# main.net
KiCad netlist of a schematic drawn in EAGLE
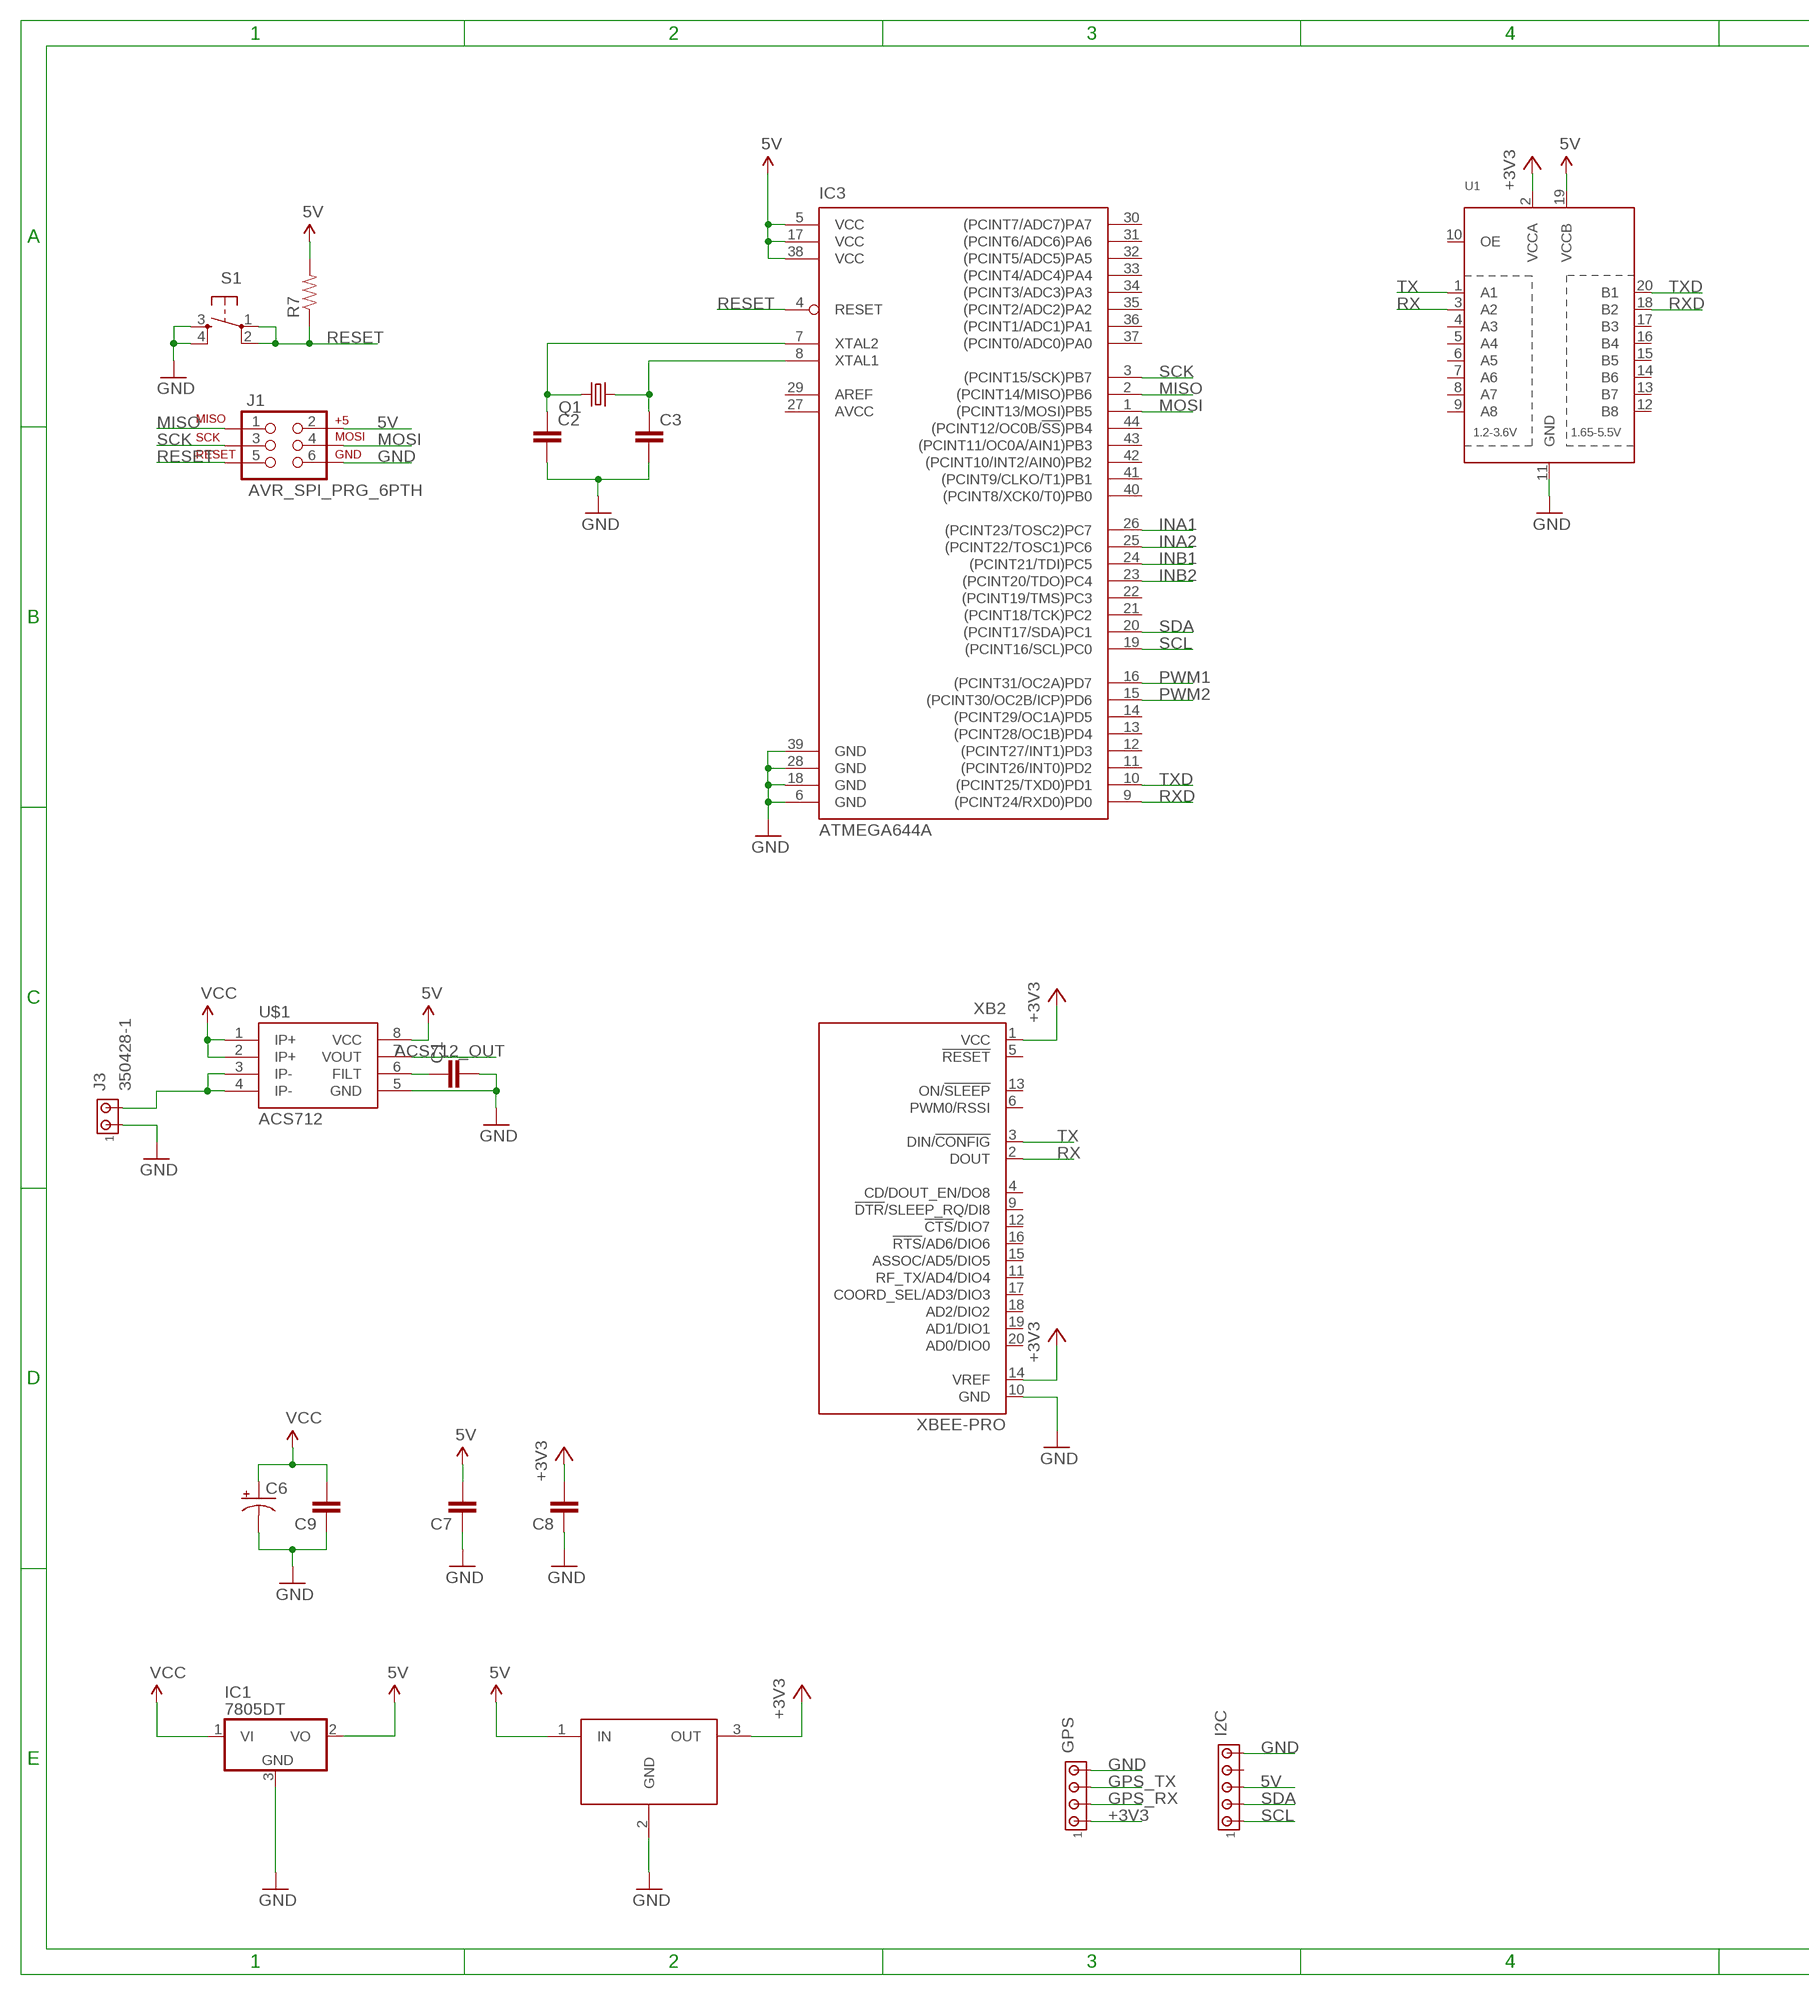
[diagram p0: schematic, sheet 1, part 1 of 2]
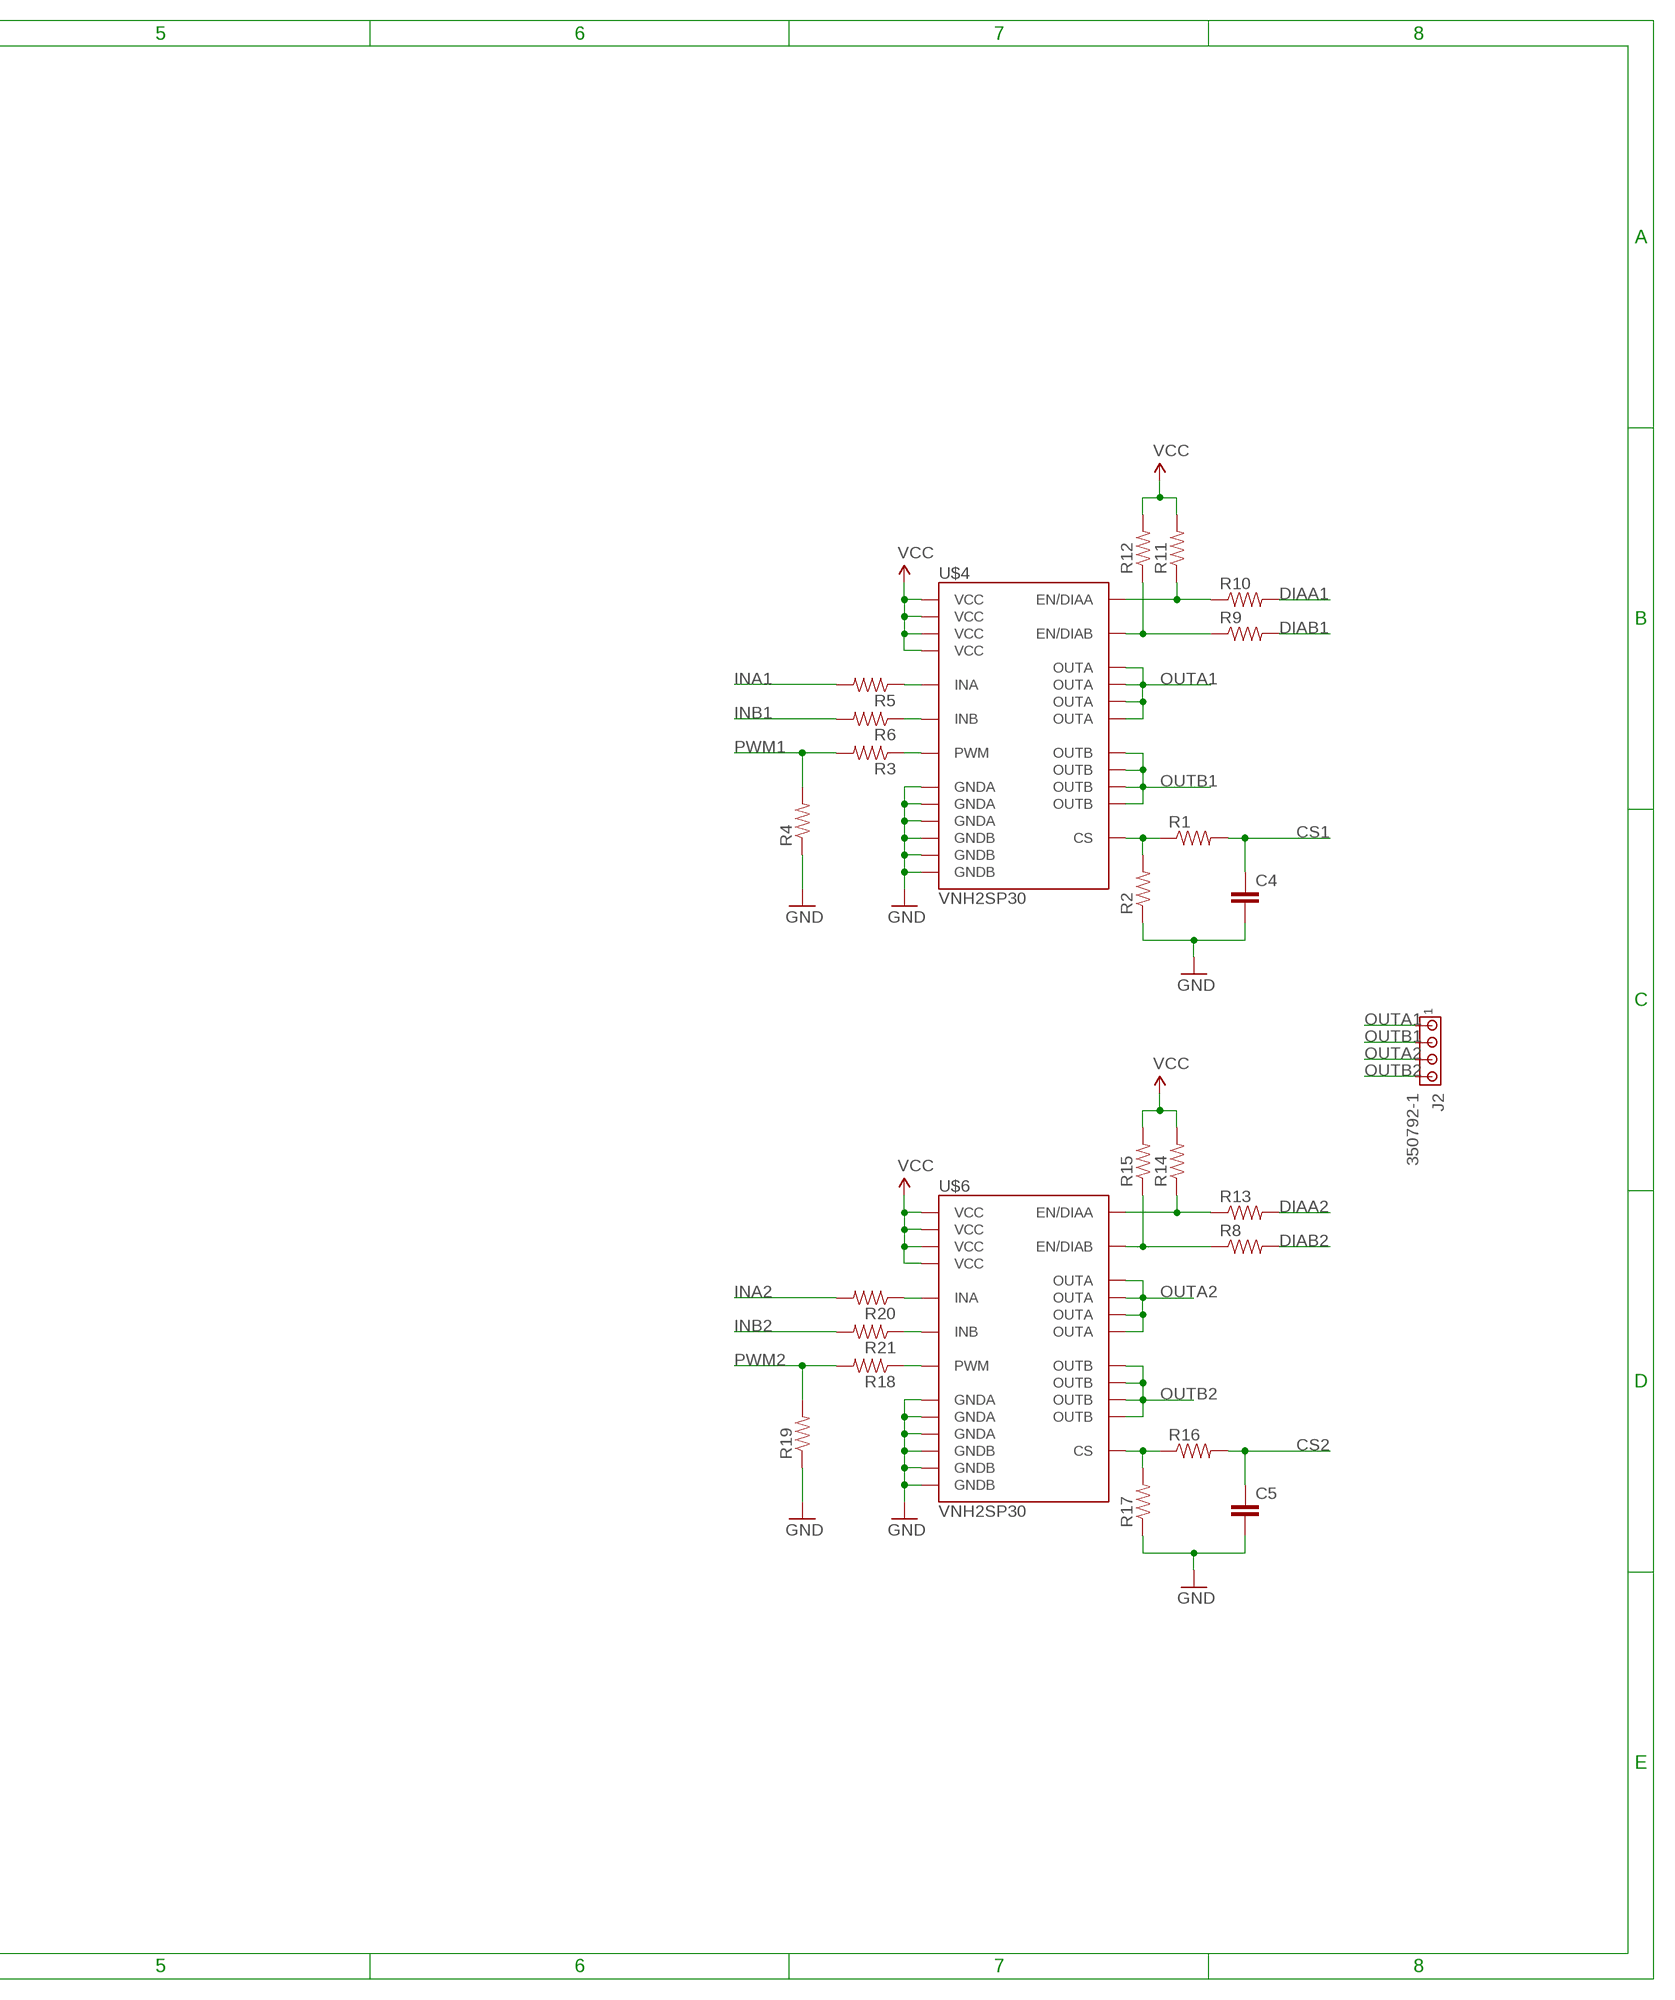
[diagram p1: schematic, sheet 1, part 2 of 2]

(export (version "E")
  (design (tool "Eeschema 10.0.6"))
  (components
    (comp (ref "C1")
      (value "CAP0603-CAP")
      (footprint "eagle-import:0603-CAP")
      (libsource (lib "eagle-import") (part "CAP0603-CAP"))
    )
    (comp (ref "C2")
      (value "CAP0603-CAP")
      (footprint "eagle-import:0603-CAP")
      (libsource (lib "eagle-import") (part "CAP0603-CAP"))
    )
    (comp (ref "C3")
      (value "CAP0603-CAP")
      (footprint "eagle-import:0603-CAP")
      (libsource (lib "eagle-import") (part "CAP0603-CAP"))
    )
    (comp (ref "C4")
      (value "CAP0603-CAP")
      (footprint "eagle-import:0603-CAP")
      (libsource (lib "eagle-import") (part "CAP0603-CAP"))
    )
    (comp (ref "C5")
      (value "CAP0603-CAP")
      (footprint "eagle-import:0603-CAP")
      (libsource (lib "eagle-import") (part "CAP0603-CAP"))
    )
    (comp (ref "C6")
      (value "CPOL-US140CLH-1010")
      (footprint "eagle-import:140CLH-1010")
      (libsource (lib "eagle-import") (part "CPOL-US140CLH-1010"))
    )
    (comp (ref "C7")
      (value "CAP0603-CAP")
      (footprint "eagle-import:0603-CAP")
      (libsource (lib "eagle-import") (part "CAP0603-CAP"))
    )
    (comp (ref "C8")
      (value "CAP0603-CAP")
      (footprint "eagle-import:0603-CAP")
      (libsource (lib "eagle-import") (part "CAP0603-CAP"))
    )
    (comp (ref "C9")
      (value "CAP0603-CAP")
      (footprint "eagle-import:0603-CAP")
      (libsource (lib "eagle-import") (part "CAP0603-CAP"))
    )
    (comp (ref "GPS")
      (value "MTA04-100")
      (footprint "eagle-import:10X04MTA")
      (libsource (lib "eagle-import") (part "MTA04-100"))
    )
    (comp (ref "I2C")
      (value "MTA05-100")
      (footprint "eagle-import:10X05MTA")
      (libsource (lib "eagle-import") (part "MTA05-100"))
    )
    (comp (ref "IC1")
      (value "7805DT")
      (footprint "eagle-import:TO252")
      (libsource (lib "eagle-import") (part "78DT05"))
    )
    (comp (ref "IC3")
      (value "ATMEGA644A")
      (footprint "eagle-import:TQFP44")
      (fields (field (name "MPN") "ATMEGA644PV-10AU"))
      (libsource (lib "eagle-import") (part "ATMEGA644A"))
    )
    (comp (ref "J1")
      (value "AVR_SPI_PRG_6PTH")
      (footprint "eagle-import:2X3")
      (libsource (lib "eagle-import") (part "AVR_SPI_PRG_6PTH"))
    )
    (comp (ref "J2")
      (value "350792-1")
      (footprint "eagle-import:350792-1")
      (libsource (lib "eagle-import") (part "350792-1"))
    )
    (comp (ref "J3")
      (value "350428-1")
      (footprint "eagle-import:350428-1")
      (libsource (lib "eagle-import") (part "350428-1"))
    )
    (comp (ref "LM3940(SOT223)")
      (value "LM3940 SOT223")
      (footprint "eagle-import:SOT223")
      (libsource (lib "eagle-import") (part "LM3940IMP-3.3"))
    )
    (comp (ref "Q1")
      (value "CRYSTALHC49UP")
      (footprint "eagle-import:HC49UP")
      (libsource (lib "eagle-import") (part "CRYSTALHC49UP"))
    )
    (comp (ref "R1")
      (value "RESISTOR0603-RES")
      (footprint "eagle-import:0603-RES")
      (libsource (lib "eagle-import") (part "RESISTOR0603-RES"))
    )
    (comp (ref "R2")
      (value "RESISTOR0603-RES")
      (footprint "eagle-import:0603-RES")
      (libsource (lib "eagle-import") (part "RESISTOR0603-RES"))
    )
    (comp (ref "R3")
      (value "RESISTOR0603-RES")
      (footprint "eagle-import:0603-RES")
      (libsource (lib "eagle-import") (part "RESISTOR0603-RES"))
    )
    (comp (ref "R4")
      (value "RESISTOR0603-RES")
      (footprint "eagle-import:0603-RES")
      (libsource (lib "eagle-import") (part "RESISTOR0603-RES"))
    )
    (comp (ref "R5")
      (value "RESISTOR0603-RES")
      (footprint "eagle-import:0603-RES")
      (libsource (lib "eagle-import") (part "RESISTOR0603-RES"))
    )
    (comp (ref "R6")
      (value "RESISTOR0603-RES")
      (footprint "eagle-import:0603-RES")
      (libsource (lib "eagle-import") (part "RESISTOR0603-RES"))
    )
    (comp (ref "R7")
      (value "RESISTOR0603-RES")
      (footprint "eagle-import:0603-RES")
      (libsource (lib "eagle-import") (part "RESISTOR0603-RES"))
    )
    (comp (ref "R8")
      (value "RESISTOR0603-RES")
      (footprint "eagle-import:0603-RES")
      (libsource (lib "eagle-import") (part "RESISTOR0603-RES"))
    )
    (comp (ref "R9")
      (value "RESISTOR0603-RES")
      (footprint "eagle-import:0603-RES")
      (libsource (lib "eagle-import") (part "RESISTOR0603-RES"))
    )
    (comp (ref "R10")
      (value "RESISTOR0603-RES")
      (footprint "eagle-import:0603-RES")
      (libsource (lib "eagle-import") (part "RESISTOR0603-RES"))
    )
    (comp (ref "R11")
      (value "RESISTOR0603-RES")
      (footprint "eagle-import:0603-RES")
      (libsource (lib "eagle-import") (part "RESISTOR0603-RES"))
    )
    (comp (ref "R12")
      (value "RESISTOR0603-RES")
      (footprint "eagle-import:0603-RES")
      (libsource (lib "eagle-import") (part "RESISTOR0603-RES"))
    )
    (comp (ref "R13")
      (value "RESISTOR0603-RES")
      (footprint "eagle-import:0603-RES")
      (libsource (lib "eagle-import") (part "RESISTOR0603-RES"))
    )
    (comp (ref "R14")
      (value "RESISTOR0603-RES")
      (footprint "eagle-import:0603-RES")
      (libsource (lib "eagle-import") (part "RESISTOR0603-RES"))
    )
    (comp (ref "R15")
      (value "RESISTOR0603-RES")
      (footprint "eagle-import:0603-RES")
      (libsource (lib "eagle-import") (part "RESISTOR0603-RES"))
    )
    (comp (ref "R16")
      (value "RESISTOR0603-RES")
      (footprint "eagle-import:0603-RES")
      (libsource (lib "eagle-import") (part "RESISTOR0603-RES"))
    )
    (comp (ref "R17")
      (value "RESISTOR0603-RES")
      (footprint "eagle-import:0603-RES")
      (libsource (lib "eagle-import") (part "RESISTOR0603-RES"))
    )
    (comp (ref "R18")
      (value "RESISTOR0603-RES")
      (footprint "eagle-import:0603-RES")
      (libsource (lib "eagle-import") (part "RESISTOR0603-RES"))
    )
    (comp (ref "R19")
      (value "RESISTOR0603-RES")
      (footprint "eagle-import:0603-RES")
      (libsource (lib "eagle-import") (part "RESISTOR0603-RES"))
    )
    (comp (ref "R20")
      (value "RESISTOR0603-RES")
      (footprint "eagle-import:0603-RES")
      (libsource (lib "eagle-import") (part "RESISTOR0603-RES"))
    )
    (comp (ref "R21")
      (value "RESISTOR0603-RES")
      (footprint "eagle-import:0603-RES")
      (libsource (lib "eagle-import") (part "RESISTOR0603-RES"))
    )
    (comp (ref "S1")
      (value "TAC_SWITCHSMD")
      (footprint "eagle-import:TACTILE_SWITCH_SMD")
      (libsource (lib "eagle-import") (part "TAC_SWITCHSMD"))
    )
    (comp (ref "U$1")
      (value "ACS712")
      (footprint "eagle-import:SO08")
      (libsource (lib "eagle-import") (part "ACS712"))
    )
    (comp (ref "U$4")
      (value "VNH2SP30")
      (footprint "eagle-import:VNH2SP30")
      (libsource (lib "eagle-import") (part "VNH2SP30"))
    )
    (comp (ref "U$6")
      (value "VNH2SP30")
      (footprint "eagle-import:VNH2SP30")
      (libsource (lib "eagle-import") (part "VNH2SP30"))
    )
    (comp (ref "U1")
      (value "TXB0108PWR")
      (footprint "eagle-import:TSSOP20")
      (libsource (lib "eagle-import") (part "TXB0108PWR"))
    )
    (comp (ref "XB2")
      (value "XBEE-PRO")
      (footprint "eagle-import:XBEE-PRO")
      (fields (field (name "MPN") "XBP24-AWI-001"))
      (libsource (lib "eagle-import") (part "XBEE-PRO"))
    )
  )
  (nets
    (net (code "1") (name "+3V3") (class "Default")
      (node (ref "C8") (pin "2") (pinfunction "2_2") (pintype "passive"))
      (node (ref "GPS") (pin "1") (pinfunction "1_1") (pintype "passive"))
      (node (ref "LM3940(SOT223)") (pin "3") (pinfunction "OUT_3") (pintype "power_in"))
      (node (ref "U1") (pin "2") (pinfunction "VCCA_2") (pintype "bidirectional"))
      (node (ref "XB2") (pin "1") (pinfunction "VCC_1") (pintype "power_in"))
      (node (ref "XB2") (pin "14") (pinfunction "VREF_14") (pintype "input"))
    )
    (net (code "2") (name "/ACS712_OUT") (class "Default")
      (node (ref "U$1") (pin "7") (pinfunction "VOUT_7") (pintype "bidirectional"))
    )
    (net (code "3") (name "/AVCC") (class "Default")
      (node (ref "IC3") (pin "27") (pinfunction "AVCC_27") (pintype "power_in"))
    )
    (net (code "4") (name "/CS1") (class "Default")
      (node (ref "C4") (pin "1") (pinfunction "1_1") (pintype "passive"))
      (node (ref "R1") (pin "2") (pinfunction "2_2") (pintype "passive"))
    )
    (net (code "5") (name "/CS2") (class "Default")
      (node (ref "C5") (pin "1") (pinfunction "1_1") (pintype "passive"))
      (node (ref "R16") (pin "2") (pinfunction "2_2") (pintype "passive"))
    )
    (net (code "6") (name "/DIAA1") (class "Default")
      (node (ref "R10") (pin "2") (pinfunction "2_2") (pintype "passive"))
    )
    (net (code "7") (name "/DIAA2") (class "Default")
      (node (ref "R13") (pin "2") (pinfunction "2_2") (pintype "passive"))
    )
    (net (code "8") (name "/DIAB1") (class "Default")
      (node (ref "R9") (pin "2") (pinfunction "2_2") (pintype "passive"))
    )
    (net (code "9") (name "/DIAB2") (class "Default")
      (node (ref "R8") (pin "2") (pinfunction "2_2") (pintype "passive"))
    )
    (net (code "10") (name "/GPS_RX") (class "Default")
      (node (ref "GPS") (pin "2") (pinfunction "2_2") (pintype "passive"))
    )
    (net (code "11") (name "/GPS_TX") (class "Default")
      (node (ref "GPS") (pin "3") (pinfunction "3_3") (pintype "passive"))
    )
    (net (code "12") (name "/INA1") (class "Default")
      (node (ref "IC3") (pin "26") (pinfunction "(PCINT23/TOSC2)PC7_26") (pintype "output"))
      (node (ref "R5") (pin "2") (pinfunction "2_2") (pintype "passive"))
    )
    (net (code "13") (name "/INA2") (class "Default")
      (node (ref "IC3") (pin "25") (pinfunction "(PCINT22/TOSC1)PC6_25") (pintype "output"))
      (node (ref "R20") (pin "2") (pinfunction "2_2") (pintype "passive"))
    )
    (net (code "14") (name "/INB1") (class "Default")
      (node (ref "IC3") (pin "24") (pinfunction "(PCINT21/TDI)PC5_24") (pintype "output"))
      (node (ref "R6") (pin "2") (pinfunction "2_2") (pintype "passive"))
    )
    (net (code "15") (name "/INB2") (class "Default")
      (node (ref "IC3") (pin "23") (pinfunction "(PCINT20/TDO)PC4_23") (pintype "output"))
      (node (ref "R21") (pin "2") (pinfunction "2_2") (pintype "passive"))
    )
    (net (code "16") (name "/MISO") (class "Default")
      (node (ref "IC3") (pin "2") (pinfunction "(PCINT14/MISO)PB6_2") (pintype "bidirectional"))
      (node (ref "J1") (pin "1") (pinfunction "1_1") (pintype "passive"))
    )
    (net (code "17") (name "/MOSI") (class "Default")
      (node (ref "IC3") (pin "1") (pinfunction "(PCINT13/MOSI)PB5_1") (pintype "bidirectional"))
      (node (ref "J1") (pin "4") (pinfunction "4_4") (pintype "passive"))
    )
    (net (code "18") (name "/OUTA1") (class "Default")
      (node (ref "J2") (pin "1") (pinfunction "1_1") (pintype "passive"))
      (node (ref "U$4") (pin "1") (pinfunction "OUTA_1") (pintype "bidirectional"))
      (node (ref "U$4") (pin "25") (pinfunction "OUTA_25") (pintype "bidirectional"))
      (node (ref "U$4") (pin "30") (pinfunction "OUTA_30") (pintype "bidirectional"))
      (node (ref "U$4") (pin "SLUG3") (pinfunction "OUTA_SLUG3") (pintype "bidirectional"))
    )
    (net (code "19") (name "/OUTA2") (class "Default")
      (node (ref "J2") (pin "3") (pinfunction "3_3") (pintype "passive"))
      (node (ref "U$6") (pin "1") (pinfunction "OUTA_1") (pintype "bidirectional"))
      (node (ref "U$6") (pin "25") (pinfunction "OUTA_25") (pintype "bidirectional"))
      (node (ref "U$6") (pin "30") (pinfunction "OUTA_30") (pintype "bidirectional"))
      (node (ref "U$6") (pin "SLUG3") (pinfunction "OUTA_SLUG3") (pintype "bidirectional"))
    )
    (net (code "20") (name "/OUTB1") (class "Default")
      (node (ref "J2") (pin "2") (pinfunction "2_2") (pintype "passive"))
      (node (ref "U$4") (pin "15") (pinfunction "OUTB_15") (pintype "bidirectional"))
      (node (ref "U$4") (pin "16") (pinfunction "OUTB_16") (pintype "bidirectional"))
      (node (ref "U$4") (pin "21") (pinfunction "OUTB_21") (pintype "bidirectional"))
      (node (ref "U$4") (pin "SLUG2") (pinfunction "OUTB_SLUG2") (pintype "bidirectional"))
    )
    (net (code "21") (name "/OUTB2") (class "Default")
      (node (ref "J2") (pin "4") (pinfunction "4_4") (pintype "passive"))
      (node (ref "U$6") (pin "15") (pinfunction "OUTB_15") (pintype "bidirectional"))
      (node (ref "U$6") (pin "16") (pinfunction "OUTB_16") (pintype "bidirectional"))
      (node (ref "U$6") (pin "21") (pinfunction "OUTB_21") (pintype "bidirectional"))
      (node (ref "U$6") (pin "SLUG2") (pinfunction "OUTB_SLUG2") (pintype "bidirectional"))
    )
    (net (code "22") (name "/PWM1") (class "Default")
      (node (ref "IC3") (pin "16") (pinfunction "(PCINT31/OC2A)PD7_16") (pintype "bidirectional"))
      (node (ref "R3") (pin "2") (pinfunction "2_2") (pintype "passive"))
      (node (ref "R4") (pin "2") (pinfunction "2_2") (pintype "passive"))
    )
    (net (code "23") (name "/PWM2") (class "Default")
      (node (ref "IC3") (pin "15") (pinfunction "(PCINT30/OC2B/ICP)PD6_15") (pintype "bidirectional"))
      (node (ref "R18") (pin "2") (pinfunction "2_2") (pintype "passive"))
      (node (ref "R19") (pin "2") (pinfunction "2_2") (pintype "passive"))
    )
    (net (code "24") (name "/RESET") (class "Default")
      (node (ref "IC3") (pin "4") (pinfunction "RESET_4") (pintype "input"))
      (node (ref "J1") (pin "5") (pinfunction "5_5") (pintype "passive"))
      (node (ref "R7") (pin "1") (pinfunction "1_1") (pintype "passive"))
      (node (ref "S1") (pin "1") (pinfunction "1_1") (pintype "passive"))
      (node (ref "S1") (pin "2") (pinfunction "2_2") (pintype "passive"))
    )
    (net (code "25") (name "/RX") (class "Default")
      (node (ref "U1") (pin "3") (pinfunction "A2_3") (pintype "bidirectional"))
      (node (ref "XB2") (pin "2") (pinfunction "DOUT_2") (pintype "output"))
    )
    (net (code "26") (name "/RXD") (class "Default")
      (node (ref "IC3") (pin "9") (pinfunction "(PCINT24/RXD0)PD0_9") (pintype "bidirectional"))
      (node (ref "U1") (pin "18") (pinfunction "B2_18") (pintype "bidirectional"))
    )
    (net (code "27") (name "/SCK") (class "Default")
      (node (ref "IC3") (pin "3") (pinfunction "(PCINT15/SCK)PB7_3") (pintype "bidirectional"))
      (node (ref "J1") (pin "3") (pinfunction "3_3") (pintype "passive"))
    )
    (net (code "28") (name "/SCL") (class "Default")
      (node (ref "I2C") (pin "1") (pinfunction "1_1") (pintype "passive"))
      (node (ref "IC3") (pin "19") (pinfunction "(PCINT16/SCL)PC0_19") (pintype "output"))
    )
    (net (code "29") (name "/SDA") (class "Default")
      (node (ref "I2C") (pin "2") (pinfunction "2_2") (pintype "passive"))
      (node (ref "IC3") (pin "20") (pinfunction "(PCINT17/SDA)PC1_20") (pintype "output"))
    )
    (net (code "30") (name "/TX") (class "Default")
      (node (ref "U1") (pin "1") (pinfunction "A1_1") (pintype "bidirectional"))
      (node (ref "XB2") (pin "3") (pinfunction "DIN/~{CONFIG}_3") (pintype "input"))
    )
    (net (code "31") (name "/TXD") (class "Default")
      (node (ref "IC3") (pin "10") (pinfunction "(PCINT25/TXD0)PD1_10") (pintype "bidirectional"))
      (node (ref "U1") (pin "20") (pinfunction "B1_20") (pintype "bidirectional"))
    )
    (net (code "32") (name "5V") (class "Default")
      (node (ref "C7") (pin "2") (pinfunction "2_2") (pintype "passive"))
      (node (ref "I2C") (pin "3") (pinfunction "3_3") (pintype "passive"))
      (node (ref "IC1") (pin "2") (pinfunction "VO_2") (pintype "passive"))
      (node (ref "IC3") (pin "17") (pinfunction "VCC_17") (pintype "power_in"))
      (node (ref "IC3") (pin "38") (pinfunction "VCC_38") (pintype "power_in"))
      (node (ref "IC3") (pin "5") (pinfunction "VCC_5") (pintype "power_in"))
      (node (ref "J1") (pin "2") (pinfunction "2_2") (pintype "passive"))
      (node (ref "LM3940(SOT223)") (pin "1") (pinfunction "IN_1") (pintype "power_in"))
      (node (ref "R7") (pin "2") (pinfunction "2_2") (pintype "passive"))
      (node (ref "U$1") (pin "8") (pinfunction "VCC_8") (pintype "bidirectional"))
      (node (ref "U1") (pin "19") (pinfunction "VCCB_19") (pintype "bidirectional"))
    )
    (net (code "33") (name "GND") (class "Default")
      (node (ref "C1") (pin "2") (pinfunction "2_2") (pintype "passive"))
      (node (ref "C2") (pin "2") (pinfunction "2_2") (pintype "passive"))
      (node (ref "C3") (pin "2") (pinfunction "2_2") (pintype "passive"))
      (node (ref "C4") (pin "2") (pinfunction "2_2") (pintype "passive"))
      (node (ref "C5") (pin "2") (pinfunction "2_2") (pintype "passive"))
      (node (ref "C6") (pin "-") (pinfunction "-_-") (pintype "passive"))
      (node (ref "C7") (pin "1") (pinfunction "1_1") (pintype "passive"))
      (node (ref "C8") (pin "1") (pinfunction "1_1") (pintype "passive"))
      (node (ref "C9") (pin "1") (pinfunction "1_1") (pintype "passive"))
      (node (ref "GPS") (pin "4") (pinfunction "4_4") (pintype "passive"))
      (node (ref "I2C") (pin "5") (pinfunction "5_5") (pintype "passive"))
      (node (ref "IC1") (pin "3") (pinfunction "GND_3") (pintype "passive"))
      (node (ref "IC3") (pin "18") (pinfunction "GND_18") (pintype "power_in"))
      (node (ref "IC3") (pin "28") (pinfunction "GND_28") (pintype "power_in"))
      (node (ref "IC3") (pin "39") (pinfunction "GND_39") (pintype "power_in"))
      (node (ref "IC3") (pin "6") (pinfunction "GND_6") (pintype "power_in"))
      (node (ref "J1") (pin "6") (pinfunction "6_6") (pintype "passive"))
      (node (ref "J3") (pin "1") (pinfunction "1_1") (pintype "passive"))
      (node (ref "LM3940(SOT223)") (pin "2") (pinfunction "GND_2") (pintype "power_in"))
      (node (ref "R17") (pin "1") (pinfunction "1_1") (pintype "passive"))
      (node (ref "R19") (pin "1") (pinfunction "1_1") (pintype "passive"))
      (node (ref "R2") (pin "1") (pinfunction "1_1") (pintype "passive"))
      (node (ref "R4") (pin "1") (pinfunction "1_1") (pintype "passive"))
      (node (ref "S1") (pin "3") (pinfunction "3_3") (pintype "passive"))
      (node (ref "S1") (pin "4") (pinfunction "4_4") (pintype "passive"))
      (node (ref "U$1") (pin "5") (pinfunction "GND_5") (pintype "bidirectional"))
      (node (ref "U$4") (pin "18") (pinfunction "GNDB_18") (pintype "bidirectional"))
      (node (ref "U$4") (pin "19") (pinfunction "GNDB_19") (pintype "bidirectional"))
      (node (ref "U$4") (pin "20") (pinfunction "GNDB_20") (pintype "bidirectional"))
      (node (ref "U$4") (pin "26") (pinfunction "GNDA_26") (pintype "bidirectional"))
      (node (ref "U$4") (pin "27") (pinfunction "GNDA_27") (pintype "bidirectional"))
      (node (ref "U$4") (pin "28") (pinfunction "GNDA_28") (pintype "bidirectional"))
      (node (ref "U$6") (pin "18") (pinfunction "GNDB_18") (pintype "bidirectional"))
      (node (ref "U$6") (pin "19") (pinfunction "GNDB_19") (pintype "bidirectional"))
      (node (ref "U$6") (pin "20") (pinfunction "GNDB_20") (pintype "bidirectional"))
      (node (ref "U$6") (pin "26") (pinfunction "GNDA_26") (pintype "bidirectional"))
      (node (ref "U$6") (pin "27") (pinfunction "GNDA_27") (pintype "bidirectional"))
      (node (ref "U$6") (pin "28") (pinfunction "GNDA_28") (pintype "bidirectional"))
      (node (ref "U1") (pin "11") (pinfunction "GND_11") (pintype "bidirectional"))
      (node (ref "XB2") (pin "10") (pinfunction "GND_10") (pintype "power_in"))
    )
    (net (code "34") (name "Net-(IC3-XTAL1)") (class "Default")
      (node (ref "C3") (pin "1") (pinfunction "1_1") (pintype "passive"))
      (node (ref "IC3") (pin "8") (pinfunction "XTAL1_8") (pintype "bidirectional"))
      (node (ref "Q1") (pin "1") (pinfunction "1_1") (pintype "passive"))
    )
    (net (code "35") (name "Net-(IC3-XTAL2)") (class "Default")
      (node (ref "C2") (pin "1") (pinfunction "1_1") (pintype "passive"))
      (node (ref "IC3") (pin "7") (pinfunction "XTAL2_7") (pintype "bidirectional"))
      (node (ref "Q1") (pin "2") (pinfunction "2_2") (pintype "passive"))
    )
    (net (code "36") (name "Net-(J3-Pad2)") (class "Default")
      (node (ref "J3") (pin "2") (pinfunction "2_2") (pintype "passive"))
      (node (ref "U$1") (pin "3") (pinfunction "IP-_3") (pintype "bidirectional"))
      (node (ref "U$1") (pin "4") (pinfunction "IP-_4") (pintype "bidirectional"))
    )
    (net (code "37") (name "Net-(U$1-FILT)") (class "Default")
      (node (ref "C1") (pin "1") (pinfunction "1_1") (pintype "passive"))
      (node (ref "U$1") (pin "6") (pinfunction "FILT_6") (pintype "bidirectional"))
    )
    (net (code "38") (name "Net-(U$4-CS)") (class "Default")
      (node (ref "R1") (pin "1") (pinfunction "1_1") (pintype "passive"))
      (node (ref "R2") (pin "2") (pinfunction "2_2") (pintype "passive"))
      (node (ref "U$4") (pin "9") (pinfunction "CS_9") (pintype "bidirectional"))
    )
    (net (code "39") (name "Net-(U$4-EN{slash}DIAA)") (class "Default")
      (node (ref "R10") (pin "1") (pinfunction "1_1") (pintype "passive"))
      (node (ref "R11") (pin "1") (pinfunction "1_1") (pintype "passive"))
      (node (ref "U$4") (pin "6") (pinfunction "EN/DIAA_6") (pintype "bidirectional"))
    )
    (net (code "40") (name "Net-(U$4-EN{slash}DIAB)") (class "Default")
      (node (ref "R12") (pin "1") (pinfunction "1_1") (pintype "passive"))
      (node (ref "R9") (pin "1") (pinfunction "1_1") (pintype "passive"))
      (node (ref "U$4") (pin "10") (pinfunction "EN/DIAB_10") (pintype "bidirectional"))
    )
    (net (code "41") (name "Net-(U$4-INA)") (class "Default")
      (node (ref "R5") (pin "1") (pinfunction "1_1") (pintype "passive"))
      (node (ref "U$4") (pin "5") (pinfunction "INA_5") (pintype "bidirectional"))
    )
    (net (code "42") (name "Net-(U$4-INB)") (class "Default")
      (node (ref "R6") (pin "1") (pinfunction "1_1") (pintype "passive"))
      (node (ref "U$4") (pin "11") (pinfunction "INB_11") (pintype "bidirectional"))
    )
    (net (code "43") (name "Net-(U$4-PWM)") (class "Default")
      (node (ref "R3") (pin "1") (pinfunction "1_1") (pintype "passive"))
      (node (ref "U$4") (pin "8") (pinfunction "PWM_8") (pintype "bidirectional"))
    )
    (net (code "44") (name "Net-(U$6-CS)") (class "Default")
      (node (ref "R16") (pin "1") (pinfunction "1_1") (pintype "passive"))
      (node (ref "R17") (pin "2") (pinfunction "2_2") (pintype "passive"))
      (node (ref "U$6") (pin "9") (pinfunction "CS_9") (pintype "bidirectional"))
    )
    (net (code "45") (name "Net-(U$6-EN{slash}DIAA)") (class "Default")
      (node (ref "R13") (pin "1") (pinfunction "1_1") (pintype "passive"))
      (node (ref "R14") (pin "1") (pinfunction "1_1") (pintype "passive"))
      (node (ref "U$6") (pin "6") (pinfunction "EN/DIAA_6") (pintype "bidirectional"))
    )
    (net (code "46") (name "Net-(U$6-EN{slash}DIAB)") (class "Default")
      (node (ref "R15") (pin "1") (pinfunction "1_1") (pintype "passive"))
      (node (ref "R8") (pin "1") (pinfunction "1_1") (pintype "passive"))
      (node (ref "U$6") (pin "10") (pinfunction "EN/DIAB_10") (pintype "bidirectional"))
    )
    (net (code "47") (name "Net-(U$6-INA)") (class "Default")
      (node (ref "R20") (pin "1") (pinfunction "1_1") (pintype "passive"))
      (node (ref "U$6") (pin "5") (pinfunction "INA_5") (pintype "bidirectional"))
    )
    (net (code "48") (name "Net-(U$6-INB)") (class "Default")
      (node (ref "R21") (pin "1") (pinfunction "1_1") (pintype "passive"))
      (node (ref "U$6") (pin "11") (pinfunction "INB_11") (pintype "bidirectional"))
    )
    (net (code "49") (name "Net-(U$6-PWM)") (class "Default")
      (node (ref "R18") (pin "1") (pinfunction "1_1") (pintype "passive"))
      (node (ref "U$6") (pin "8") (pinfunction "PWM_8") (pintype "bidirectional"))
    )
    (net (code "50") (name "VCC") (class "Default")
      (node (ref "C6") (pin "+") (pinfunction "+_+") (pintype "passive"))
      (node (ref "C9") (pin "2") (pinfunction "2_2") (pintype "passive"))
      (node (ref "IC1") (pin "1") (pinfunction "VI_1") (pintype "input"))
      (node (ref "R11") (pin "2") (pinfunction "2_2") (pintype "passive"))
      (node (ref "R12") (pin "2") (pinfunction "2_2") (pintype "passive"))
      (node (ref "R14") (pin "2") (pinfunction "2_2") (pintype "passive"))
      (node (ref "R15") (pin "2") (pinfunction "2_2") (pintype "passive"))
      (node (ref "U$1") (pin "1") (pinfunction "IP+_1") (pintype "bidirectional"))
      (node (ref "U$1") (pin "2") (pinfunction "IP+_2") (pintype "bidirectional"))
      (node (ref "U$4") (pin "13") (pinfunction "VCC_13") (pintype "bidirectional"))
      (node (ref "U$4") (pin "23") (pinfunction "VCC_23") (pintype "bidirectional"))
      (node (ref "U$4") (pin "3") (pinfunction "VCC_3") (pintype "bidirectional"))
      (node (ref "U$4") (pin "SLUG1") (pinfunction "VCC_SLUG1") (pintype "bidirectional"))
      (node (ref "U$6") (pin "13") (pinfunction "VCC_13") (pintype "bidirectional"))
      (node (ref "U$6") (pin "23") (pinfunction "VCC_23") (pintype "bidirectional"))
      (node (ref "U$6") (pin "3") (pinfunction "VCC_3") (pintype "bidirectional"))
      (node (ref "U$6") (pin "SLUG1") (pinfunction "VCC_SLUG1") (pintype "bidirectional"))
    )
    (net (code "51") (name "unconnected-(I2C-Pad4)") (class "Default")
      (node (ref "I2C") (pin "4") (pinfunction "4_4") (pintype "passive"))
    )
    (net (code "52") (name "unconnected-(IC3-(PCINT0{slash}ADC0)PA0-Pad37)") (class "Default")
      (node (ref "IC3") (pin "37") (pinfunction "(PCINT0/ADC0)PA0_37") (pintype "bidirectional"))
    )
    (net (code "53") (name "unconnected-(IC3-(PCINT1{slash}ADC1)PA1-Pad36)") (class "Default")
      (node (ref "IC3") (pin "36") (pinfunction "(PCINT1/ADC1)PA1_36") (pintype "bidirectional"))
    )
    (net (code "54") (name "unconnected-(IC3-(PCINT2{slash}ADC2)PA2-Pad35)") (class "Default")
      (node (ref "IC3") (pin "35") (pinfunction "(PCINT2/ADC2)PA2_35") (pintype "bidirectional"))
    )
    (net (code "55") (name "unconnected-(IC3-(PCINT3{slash}ADC3)PA3-Pad34)") (class "Default")
      (node (ref "IC3") (pin "34") (pinfunction "(PCINT3/ADC3)PA3_34") (pintype "bidirectional"))
    )
    (net (code "56") (name "unconnected-(IC3-(PCINT4{slash}ADC4)PA4-Pad33)") (class "Default")
      (node (ref "IC3") (pin "33") (pinfunction "(PCINT4/ADC4)PA4_33") (pintype "bidirectional"))
    )
    (net (code "57") (name "unconnected-(IC3-(PCINT5{slash}ADC5)PA5-Pad32)") (class "Default")
      (node (ref "IC3") (pin "32") (pinfunction "(PCINT5/ADC5)PA5_32") (pintype "bidirectional"))
    )
    (net (code "58") (name "unconnected-(IC3-(PCINT6{slash}ADC6)PA6-Pad31)") (class "Default")
      (node (ref "IC3") (pin "31") (pinfunction "(PCINT6/ADC6)PA6_31") (pintype "bidirectional"))
    )
    (net (code "59") (name "unconnected-(IC3-(PCINT7{slash}ADC7)PA7-Pad30)") (class "Default")
      (node (ref "IC3") (pin "30") (pinfunction "(PCINT7/ADC7)PA7_30") (pintype "bidirectional"))
    )
    (net (code "60") (name "unconnected-(IC3-(PCINT8{slash}XCK0{slash}T0)PB0-Pad40)") (class "Default")
      (node (ref "IC3") (pin "40") (pinfunction "(PCINT8/XCK0/T0)PB0_40") (pintype "bidirectional"))
    )
    (net (code "61") (name "unconnected-(IC3-(PCINT9{slash}CLKO{slash}T1)PB1-Pad41)") (class "Default")
      (node (ref "IC3") (pin "41") (pinfunction "(PCINT9/CLKO/T1)PB1_41") (pintype "bidirectional"))
    )
    (net (code "62") (name "unconnected-(IC3-(PCINT10{slash}INT2{slash}AIN0)PB2-Pad42)") (class "Default")
      (node (ref "IC3") (pin "42") (pinfunction "(PCINT10/INT2/AIN0)PB2_42") (pintype "bidirectional"))
    )
    (net (code "63") (name "unconnected-(IC3-(PCINT11{slash}OC0A{slash}AIN1)PB3-Pad43)") (class "Default")
      (node (ref "IC3") (pin "43") (pinfunction "(PCINT11/OC0A/AIN1)PB3_43") (pintype "bidirectional"))
    )
    (net (code "64") (name "unconnected-(IC3-(PCINT12{slash}OC0B{slash}~{SS})PB4-Pad44)") (class "Default")
      (node (ref "IC3") (pin "44") (pinfunction "(PCINT12/OC0B/~{SS})PB4_44") (pintype "bidirectional"))
    )
    (net (code "65") (name "unconnected-(IC3-(PCINT18{slash}TCK)PC2-Pad21)") (class "Default")
      (node (ref "IC3") (pin "21") (pinfunction "(PCINT18/TCK)PC2_21") (pintype "output"))
    )
    (net (code "66") (name "unconnected-(IC3-(PCINT19{slash}TMS)PC3-Pad22)") (class "Default")
      (node (ref "IC3") (pin "22") (pinfunction "(PCINT19/TMS)PC3_22") (pintype "output"))
    )
    (net (code "67") (name "unconnected-(IC3-(PCINT26{slash}INT0)PD2-Pad11)") (class "Default")
      (node (ref "IC3") (pin "11") (pinfunction "(PCINT26/INT0)PD2_11") (pintype "bidirectional"))
    )
    (net (code "68") (name "unconnected-(IC3-(PCINT27{slash}INT1)PD3-Pad12)") (class "Default")
      (node (ref "IC3") (pin "12") (pinfunction "(PCINT27/INT1)PD3_12") (pintype "bidirectional"))
    )
    (net (code "69") (name "unconnected-(IC3-(PCINT28{slash}OC1B)PD4-Pad13)") (class "Default")
      (node (ref "IC3") (pin "13") (pinfunction "(PCINT28/OC1B)PD4_13") (pintype "bidirectional"))
    )
    (net (code "70") (name "unconnected-(IC3-(PCINT29{slash}OC1A)PD5-Pad14)") (class "Default")
      (node (ref "IC3") (pin "14") (pinfunction "(PCINT29/OC1A)PD5_14") (pintype "bidirectional"))
    )
    (net (code "71") (name "unconnected-(IC3-AREF-Pad29)") (class "Default")
      (node (ref "IC3") (pin "29") (pinfunction "AREF_29") (pintype "passive"))
    )
    (net (code "72") (name "unconnected-(U1-A3-Pad4)") (class "Default")
      (node (ref "U1") (pin "4") (pinfunction "A3_4") (pintype "bidirectional"))
    )
    (net (code "73") (name "unconnected-(U1-A4-Pad5)") (class "Default")
      (node (ref "U1") (pin "5") (pinfunction "A4_5") (pintype "bidirectional"))
    )
    (net (code "74") (name "unconnected-(U1-A5-Pad6)") (class "Default")
      (node (ref "U1") (pin "6") (pinfunction "A5_6") (pintype "bidirectional"))
    )
    (net (code "75") (name "unconnected-(U1-A6-Pad7)") (class "Default")
      (node (ref "U1") (pin "7") (pinfunction "A6_7") (pintype "bidirectional"))
    )
    (net (code "76") (name "unconnected-(U1-A7-Pad8)") (class "Default")
      (node (ref "U1") (pin "8") (pinfunction "A7_8") (pintype "bidirectional"))
    )
    (net (code "77") (name "unconnected-(U1-A8-Pad9)") (class "Default")
      (node (ref "U1") (pin "9") (pinfunction "A8_9") (pintype "bidirectional"))
    )
    (net (code "78") (name "unconnected-(U1-B3-Pad17)") (class "Default")
      (node (ref "U1") (pin "17") (pinfunction "B3_17") (pintype "bidirectional"))
    )
    (net (code "79") (name "unconnected-(U1-B4-Pad16)") (class "Default")
      (node (ref "U1") (pin "16") (pinfunction "B4_16") (pintype "bidirectional"))
    )
    (net (code "80") (name "unconnected-(U1-B5-Pad15)") (class "Default")
      (node (ref "U1") (pin "15") (pinfunction "B5_15") (pintype "bidirectional"))
    )
    (net (code "81") (name "unconnected-(U1-B6-Pad14)") (class "Default")
      (node (ref "U1") (pin "14") (pinfunction "B6_14") (pintype "bidirectional"))
    )
    (net (code "82") (name "unconnected-(U1-B7-Pad13)") (class "Default")
      (node (ref "U1") (pin "13") (pinfunction "B7_13") (pintype "bidirectional"))
    )
    (net (code "83") (name "unconnected-(U1-B8-Pad12)") (class "Default")
      (node (ref "U1") (pin "12") (pinfunction "B8_12") (pintype "bidirectional"))
    )
    (net (code "84") (name "unconnected-(U1-OE-Pad10)") (class "Default")
      (node (ref "U1") (pin "10") (pinfunction "OE_10") (pintype "bidirectional"))
    )
    (net (code "85") (name "unconnected-(XB2-AD0{slash}DIO0-Pad20)") (class "Default")
      (node (ref "XB2") (pin "20") (pinfunction "AD0/DIO0_20") (pintype "bidirectional"))
    )
    (net (code "86") (name "unconnected-(XB2-AD1{slash}DIO1-Pad19)") (class "Default")
      (node (ref "XB2") (pin "19") (pinfunction "AD1/DIO1_19") (pintype "bidirectional"))
    )
    (net (code "87") (name "unconnected-(XB2-AD2{slash}DIO2-Pad18)") (class "Default")
      (node (ref "XB2") (pin "18") (pinfunction "AD2/DIO2_18") (pintype "bidirectional"))
    )
    (net (code "88") (name "unconnected-(XB2-ASSOC{slash}AD5{slash}DIO5-Pad15)") (class "Default")
      (node (ref "XB2") (pin "15") (pinfunction "ASSOC/AD5/DIO5_15") (pintype "bidirectional"))
    )
    (net (code "89") (name "unconnected-(XB2-CD{slash}DOUT_EN{slash}DO8-Pad4)") (class "Default")
      (node (ref "XB2") (pin "4") (pinfunction "CD/DOUT_EN/DO8_4") (pintype "output"))
    )
    (net (code "90") (name "unconnected-(XB2-COORD_SEL{slash}AD3{slash}DIO3-Pad17)") (class "Default")
      (node (ref "XB2") (pin "17") (pinfunction "COORD_SEL/AD3/DIO3_17") (pintype "bidirectional"))
    )
    (net (code "91") (name "unconnected-(XB2-ON{slash}~{SLEEP}-Pad13)") (class "Default")
      (node (ref "XB2") (pin "13") (pinfunction "ON/~{SLEEP}_13") (pintype "output"))
    )
    (net (code "92") (name "unconnected-(XB2-PWM0{slash}RSSI-Pad6)") (class "Default")
      (node (ref "XB2") (pin "6") (pinfunction "PWM0/RSSI_6") (pintype "output"))
    )
    (net (code "93") (name "unconnected-(XB2-RF_TX{slash}AD4{slash}DIO4-Pad11)") (class "Default")
      (node (ref "XB2") (pin "11") (pinfunction "RF_TX/AD4/DIO4_11") (pintype "bidirectional"))
    )
    (net (code "94") (name "unconnected-(XB2-~{CTS}{slash}DIO7-Pad12)") (class "Default")
      (node (ref "XB2") (pin "12") (pinfunction "~{CTS}/DIO7_12") (pintype "bidirectional"))
    )
    (net (code "95") (name "unconnected-(XB2-~{DTR}{slash}SLEEP_RQ{slash}DI8-Pad9)") (class "Default")
      (node (ref "XB2") (pin "9") (pinfunction "~{DTR}/SLEEP_RQ/DI8_9") (pintype "bidirectional"))
    )
    (net (code "96") (name "unconnected-(XB2-~{RESET}-Pad5)") (class "Default")
      (node (ref "XB2") (pin "5") (pinfunction "~{RESET}_5") (pintype "input"))
    )
    (net (code "97") (name "unconnected-(XB2-~{RTS}{slash}AD6{slash}DIO6-Pad16)") (class "Default")
      (node (ref "XB2") (pin "16") (pinfunction "~{RTS}/AD6/DIO6_16") (pintype "bidirectional"))
    )
  )
)
